# Connectors.net
KiCad netlist of a schematic drawn in Altium Designer
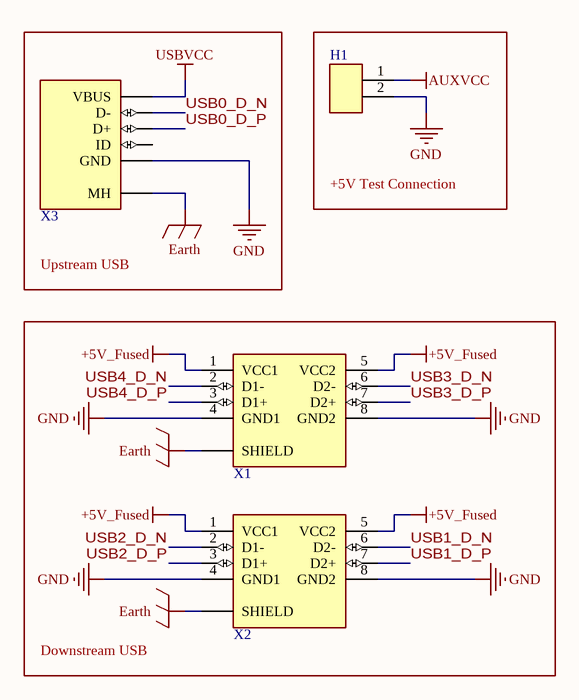
[diagram p0: Connectors.SchDoc]

(export (version "E")
  (design (tool "Eeschema 10.0.6"))
  (components
    (comp (ref "H1")
      (value "1x2 Header")
      (footprint "[Header] 1x2 Male")
      (description "2.54mm pitch")
      (libsource (lib "Connectors") (part "[Header] 1x2 Male"))
    )
    (comp (ref "X1")
      (value "USB-A")
      (footprint "[USB] Type-A Dual")
      (description "61400826021")
      (libsource (lib "Connectors") (part "[USB] Type-A Dual"))
    )
    (comp (ref "X2")
      (value "USB-A")
      (footprint "[USB] Type-A Dual")
      (description "61400826021")
      (libsource (lib "Connectors") (part "[USB] Type-A Dual"))
    )
    (comp (ref "X3")
      (value "[USB] Type-B Mini")
      (footprint "[USB] Type-B Mini")
      (description "MUSB-05-S-B-SM-A-K-TR")
      (libsource (lib "Connectors") (part "[USB] Type-B Mini"))
    )
  )
  (nets
    (net (code "1") (name "+5V_Fused") (class "Default")
      (node (ref "X1") (pin "1") (pinfunction "VCC1_1") (pintype "power_in"))
      (node (ref "X1") (pin "5") (pinfunction "VCC2_5") (pintype "power_in"))
      (node (ref "X2") (pin "1") (pinfunction "VCC1_1") (pintype "power_in"))
      (node (ref "X2") (pin "5") (pinfunction "VCC2_5") (pintype "power_in"))
    )
    (net (code "2") (name "/USB0_D_N") (class "Default")
      (node (ref "X3") (pin "2") (pinfunction "D-_2") (pintype "bidirectional"))
    )
    (net (code "3") (name "/USB0_D_P") (class "Default")
      (node (ref "X3") (pin "3") (pinfunction "D+_3") (pintype "bidirectional"))
    )
    (net (code "4") (name "/USB1_D_N") (class "Default")
      (node (ref "X2") (pin "6") (pinfunction "D2-_6") (pintype "bidirectional"))
    )
    (net (code "5") (name "/USB1_D_P") (class "Default")
      (node (ref "X2") (pin "7") (pinfunction "D2+_7") (pintype "bidirectional"))
    )
    (net (code "6") (name "/USB2_D_N") (class "Default")
      (node (ref "X2") (pin "2") (pinfunction "D1-_2") (pintype "bidirectional"))
    )
    (net (code "7") (name "/USB2_D_P") (class "Default")
      (node (ref "X2") (pin "3") (pinfunction "D1+_3") (pintype "bidirectional"))
    )
    (net (code "8") (name "/USB3_D_N") (class "Default")
      (node (ref "X1") (pin "6") (pinfunction "D2-_6") (pintype "bidirectional"))
    )
    (net (code "9") (name "/USB3_D_P") (class "Default")
      (node (ref "X1") (pin "7") (pinfunction "D2+_7") (pintype "bidirectional"))
    )
    (net (code "10") (name "/USB4_D_N") (class "Default")
      (node (ref "X1") (pin "2") (pinfunction "D1-_2") (pintype "bidirectional"))
    )
    (net (code "11") (name "/USB4_D_P") (class "Default")
      (node (ref "X1") (pin "3") (pinfunction "D1+_3") (pintype "bidirectional"))
    )
    (net (code "12") (name "AUXVCC") (class "Default") (node (ref "H1") (pin "1") (pintype "passive")))
    (net (code "13") (name "Earth") (class "Default")
      (node (ref "X1") (pin "MH") (pinfunction "SHIELD_MH") (pintype "passive"))
      (node (ref "X2") (pin "MH") (pinfunction "SHIELD_MH") (pintype "passive"))
      (node (ref "X3") (pin "MH") (pinfunction "MH_MH") (pintype "power_in"))
    )
    (net (code "14") (name "GND") (class "Default")
      (node (ref "H1") (pin "2") (pintype "passive"))
      (node (ref "X1") (pin "4") (pinfunction "GND1_4") (pintype "power_in"))
      (node (ref "X1") (pin "8") (pinfunction "GND2_8") (pintype "power_in"))
      (node (ref "X2") (pin "4") (pinfunction "GND1_4") (pintype "power_in"))
      (node (ref "X2") (pin "8") (pinfunction "GND2_8") (pintype "power_in"))
      (node (ref "X3") (pin "5") (pinfunction "GND_5") (pintype "power_in"))
    )
    (net (code "15") (name "USBVCC") (class "Default")
      (node (ref "X3") (pin "1") (pinfunction "VBUS_1") (pintype "power_in"))
    )
    (net (code "16") (name "unconnected-(X3-ID-Pad4)") (class "Default")
      (node (ref "X3") (pin "4") (pinfunction "ID_4") (pintype "bidirectional"))
    )
  )
)
